# CarrierConnector.net
KiCad netlist of a schematic drawn in Altium Designer
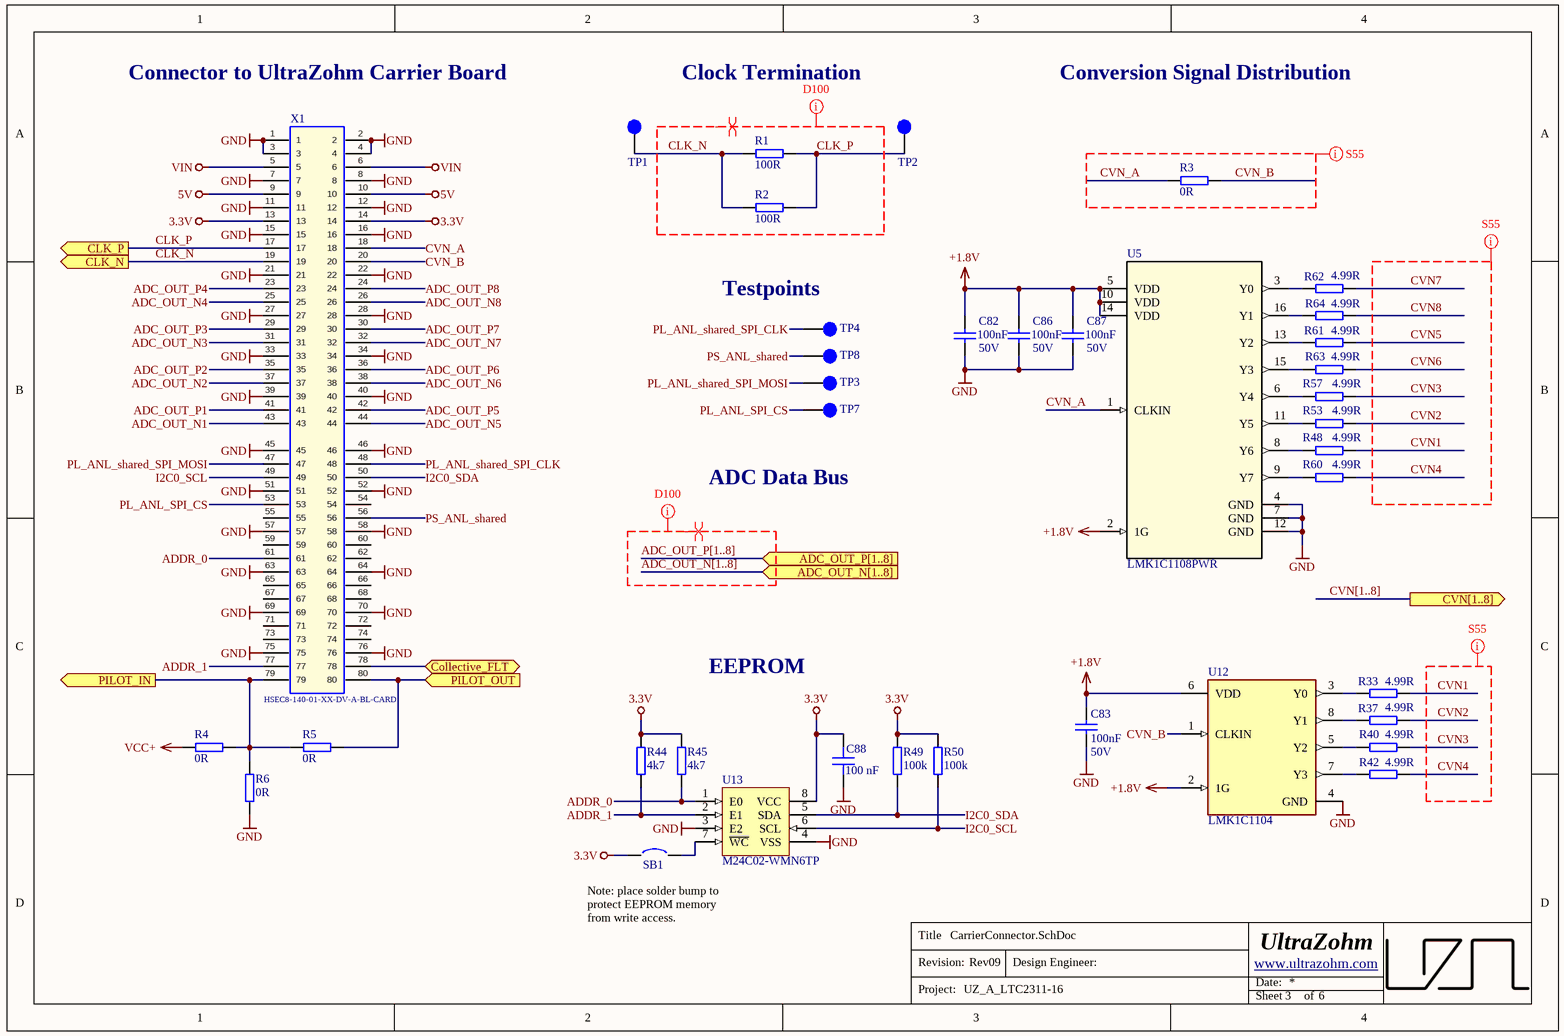
[diagram p0: CarrierConnector.SchDoc]

(export (version "E")
  (design (tool "Eeschema 10.0.6"))
  (components
    (comp (ref "C82")
      (value "100nF")
      (footprint "CAPC1608X07N")
      (fields
        (field (name "MF") "Yageo")
        (field (name "MPN") "CC0603KRX7R9BB104")
        (field (name "VOLTAGE") "50V")
      )
      (libsource (lib "UltraZohm_ADC") (part "Cap_0603"))
    )
    (comp (ref "C83")
      (value "100nF")
      (footprint "CAPC1608X07N")
      (fields
        (field (name "MF") "Yageo")
        (field (name "MPN") "CC0603KRX7R9BB104")
        (field (name "VOLTAGE") "50V")
      )
      (libsource (lib "UltraZohm_ADC") (part "Cap_0603"))
    )
    (comp (ref "C86")
      (value "100nF")
      (footprint "CAPC1608X07N")
      (fields
        (field (name "MF") "Yageo")
        (field (name "MPN") "CC0603KRX7R9BB104")
        (field (name "VOLTAGE") "50V")
      )
      (libsource (lib "UltraZohm_ADC") (part "Cap_0603"))
    )
    (comp (ref "C87")
      (value "100nF")
      (footprint "CAPC1608X07N")
      (fields
        (field (name "MF") "Yageo")
        (field (name "MPN") "CC0603KRX7R9BB104")
        (field (name "VOLTAGE") "50V")
      )
      (libsource (lib "UltraZohm_ADC") (part "Cap_0603"))
    )
    (comp (ref "C88")
      (value "100 nF")
      (footprint "C_0603")
      (description "Capacitor 0603, 6.3 VDC, 100 nF, X5R")
      (fields
        (field (name "MANUFACTURER PART NUMBER") "C0603C104K9PACTU")
        (field (name "MANUFACTURER") "KEMET")
        (field (name "CREATED FROM") "MGremer")
      )
      (libsource (lib "user") (part "Capacitor"))
    )
    (comp (ref "R1")
      (value "100R")
      (footprint "RESC1608X06N")
      (fields
        (field (name "MF") "Yageo")
        (field (name "MPN") "AC0603FR-13100RL")
        (field (name "TOLERANCE") "1%")
      )
      (libsource (lib "UltraZohm_ADC") (part "R_0603"))
    )
    (comp (ref "R2")
      (value "100R")
      (footprint "RESC1608X06N")
      (fields
        (field (name "MF") "Yageo")
        (field (name "MPN") "AC0603FR-13100RL")
        (field (name "TOLERANCE") "1%")
      )
      (libsource (lib "UltraZohm_ADC") (part "R_0603"))
    )
    (comp (ref "R3")
      (value "0R")
      (footprint "RESC1608X06N")
      (fields (field (name "MF") "Vishay / Dale") (field (name "MPN") "CRCW06030000Z0EBC"))
      (libsource (lib "UltraZohm_ADC") (part "R_0603"))
    )
    (comp (ref "R4")
      (value "0R")
      (footprint "RESC1608X06N")
      (fields (field (name "MF") "Vishay / Dale") (field (name "MPN") "CRCW06030000Z0EBC"))
      (libsource (lib "UltraZohm_ADC") (part "R_0603"))
    )
    (comp (ref "R5")
      (value "0R")
      (footprint "RESC1608X06N")
      (fields (field (name "MF") "Vishay / Dale") (field (name "MPN") "CRCW06030000Z0EBC"))
      (libsource (lib "UltraZohm_ADC") (part "R_0603"))
    )
    (comp (ref "R6")
      (value "0R")
      (footprint "RESC1608X06N")
      (fields (field (name "MF") "Vishay / Dale") (field (name "MPN") "CRCW06030000Z0EBC"))
      (libsource (lib "UltraZohm_ADC") (part "R_0603"))
    )
    (comp (ref "R33")
      (value "4.99R")
      (footprint "RESC1608X06N")
      (fields
        (field (name "MF") "Vishay / Dale")
        (field (name "MPN") "CRCW06034R99FKEA")
        (field (name "TOLERANCE") "1%")
      )
      (libsource (lib "UltraZohm_ADC") (part "R_0603"))
    )
    (comp (ref "R37")
      (value "4.99R")
      (footprint "RESC1608X06N")
      (fields
        (field (name "MF") "Vishay / Dale")
        (field (name "MPN") "CRCW06034R99FKEA")
        (field (name "TOLERANCE") "1%")
      )
      (libsource (lib "UltraZohm_ADC") (part "R_0603"))
    )
    (comp (ref "R40")
      (value "4.99R")
      (footprint "RESC1608X06N")
      (fields
        (field (name "MF") "Vishay / Dale")
        (field (name "MPN") "CRCW06034R99FKEA")
        (field (name "TOLERANCE") "1%")
      )
      (libsource (lib "UltraZohm_ADC") (part "R_0603"))
    )
    (comp (ref "R42")
      (value "4.99R")
      (footprint "RESC1608X06N")
      (fields
        (field (name "MF") "Vishay / Dale")
        (field (name "MPN") "CRCW06034R99FKEA")
        (field (name "TOLERANCE") "1%")
      )
      (libsource (lib "UltraZohm_ADC") (part "R_0603"))
    )
    (comp (ref "R44")
      (value "4k7")
      (footprint "RES 0603_1608")
      (description "SMD resistor E24 series")
      (fields
        (field (name "MANUFACTURER PART NUMBER") "0603WAF4701T5E")
        (field (name "MANUFACTURER") "UNI-ROYAL")
        (field (name "CREATED FROM") "AGeiger")
      )
      (libsource (lib "user") (part "Resistor"))
    )
    (comp (ref "R45")
      (value "4k7")
      (footprint "RES 0603_1608")
      (description "SMD resistor E24 series")
      (fields
        (field (name "MANUFACTURER PART NUMBER") "0603WAF4701T5E")
        (field (name "MANUFACTURER") "UNI-ROYAL")
        (field (name "CREATED FROM") "AGeiger")
      )
      (libsource (lib "user") (part "Resistor"))
    )
    (comp (ref "R48")
      (value "4.99R")
      (footprint "RESC1608X06N")
      (fields
        (field (name "MF") "Vishay / Dale")
        (field (name "MPN") "CRCW06034R99FKEA")
        (field (name "TOLERANCE") "1%")
      )
      (libsource (lib "UltraZohm_ADC") (part "R_0603"))
    )
    (comp (ref "R49")
      (value "100k")
      (footprint "RES 0603_1608")
      (description "SMD resistor E24 series")
      (fields
        (field (name "MANUFACTURER PART NUMBER") "RK73B1JTTD104J")
        (field (name "MANUFACTURER") "KOA Speer")
        (field (name "CREATED FROM") "MGremer")
      )
      (libsource (lib "user") (part "Resistor"))
    )
    (comp (ref "R50")
      (value "100k")
      (footprint "RES 0603_1608")
      (description "SMD resistor E24 series")
      (fields
        (field (name "MANUFACTURER PART NUMBER") "RK73B1JTTD104J")
        (field (name "MANUFACTURER") "KOA Speer")
        (field (name "CREATED FROM") "MGremer")
      )
      (libsource (lib "user") (part "Resistor"))
    )
    (comp (ref "R53")
      (value "4.99R")
      (footprint "RESC1608X06N")
      (fields
        (field (name "MF") "Vishay / Dale")
        (field (name "MPN") "CRCW06034R99FKEA")
        (field (name "TOLERANCE") "1%")
      )
      (libsource (lib "UltraZohm_ADC") (part "R_0603"))
    )
    (comp (ref "R57")
      (value "4.99R")
      (footprint "RESC1608X06N")
      (fields
        (field (name "MF") "Vishay / Dale")
        (field (name "MPN") "CRCW06034R99FKEA")
        (field (name "TOLERANCE") "1%")
      )
      (libsource (lib "UltraZohm_ADC") (part "R_0603"))
    )
    (comp (ref "R60")
      (value "4.99R")
      (footprint "RESC1608X06N")
      (fields
        (field (name "MF") "Vishay / Dale")
        (field (name "MPN") "CRCW06034R99FKEA")
        (field (name "TOLERANCE") "1%")
      )
      (libsource (lib "UltraZohm_ADC") (part "R_0603"))
    )
    (comp (ref "R61")
      (value "4.99R")
      (footprint "RESC1608X06N")
      (fields
        (field (name "MF") "Vishay / Dale")
        (field (name "MPN") "CRCW06034R99FKEA")
        (field (name "TOLERANCE") "1%")
      )
      (libsource (lib "UltraZohm_ADC") (part "R_0603"))
    )
    (comp (ref "R62")
      (value "4.99R")
      (footprint "RESC1608X06N")
      (fields
        (field (name "MF") "Vishay / Dale")
        (field (name "MPN") "CRCW06034R99FKEA")
        (field (name "TOLERANCE") "1%")
      )
      (libsource (lib "UltraZohm_ADC") (part "R_0603"))
    )
    (comp (ref "R63")
      (value "4.99R")
      (footprint "RESC1608X06N")
      (fields
        (field (name "MF") "Vishay / Dale")
        (field (name "MPN") "CRCW06034R99FKEA")
        (field (name "TOLERANCE") "1%")
      )
      (libsource (lib "UltraZohm_ADC") (part "R_0603"))
    )
    (comp (ref "R64")
      (value "4.99R")
      (footprint "RESC1608X06N")
      (fields
        (field (name "MF") "Vishay / Dale")
        (field (name "MPN") "CRCW06034R99FKEA")
        (field (name "TOLERANCE") "1%")
      )
      (libsource (lib "UltraZohm_ADC") (part "R_0603"))
    )
    (comp (ref "SB1")
      (value "Solder Bump 0603")
      (footprint "SB_0603")
      (fields (field (name "CREATED FROM") "AGeiger"))
      (libsource (lib "user") (part "Solder_Bump"))
    )
    (comp (ref "TP1")
      (value "ACLK_N")
      (footprint "TP_1mm")
      (description "Testpoint 1mm")
      (fields (field (name "CREATED") "2018_06_25_AGeiger"))
      (libsource (lib "UltraZOhm_CarrierBoard") (part "TP_1mm"))
    )
    (comp (ref "TP2")
      (value "ACLK_P")
      (footprint "TP_1mm")
      (description "Testpoint 1mm")
      (fields (field (name "CREATED") "2018_06_25_AGeiger"))
      (libsource (lib "UltraZOhm_CarrierBoard") (part "TP_1mm"))
    )
    (comp (ref "TP3")
      (value "PIN47")
      (footprint "TP_1mm")
      (description "Testpoint 1mm")
      (fields (field (name "CREATED") "2018_06_25_AGeiger"))
      (libsource (lib "UltraZOhm_CarrierBoard") (part "TP_1mm"))
    )
    (comp (ref "TP4")
      (value "PIN48")
      (footprint "TP_1mm")
      (description "Testpoint 1mm")
      (fields (field (name "CREATED") "2018_06_25_AGeiger"))
      (libsource (lib "UltraZOhm_CarrierBoard") (part "TP_1mm"))
    )
    (comp (ref "TP7")
      (value "PIN53")
      (footprint "TP_1mm")
      (description "Testpoint 1mm")
      (fields (field (name "CREATED") "2018_06_25_AGeiger"))
      (libsource (lib "UltraZOhm_CarrierBoard") (part "TP_1mm"))
    )
    (comp (ref "TP8")
      (value "PIN56")
      (footprint "TP_1mm")
      (description "Testpoint 1mm")
      (fields (field (name "CREATED") "2018_06_25_AGeiger"))
      (libsource (lib "UltraZOhm_CarrierBoard") (part "TP_1mm"))
    )
    (comp (ref "U5")
      (value "LMK1C1108PWR")
      (footprint "PW0016A_M")
      (description "8-channel output LVCMOS 1.8V buffer")
      (fields (field (name "MF") "Texas Instruments"))
      (libsource (lib "UltraZohm_ADC") (part "LMK1C1108PWR"))
    )
    (comp (ref "U12")
      (value "LMK1C1104")
      (footprint "FP-PW0008A-MFG")
      (description "4-channel output LVCMOS 1.8-V buffer")
      (fields
        (field (name "MANUFACTURER") "Texas Instruments")
        (field (name "MANUFACTURER PART NUMBER") "LMK1C1104PWR")
      )
      (libsource (lib "UltraZohm_ADC") (part "LMK1C1104"))
    )
    (comp (ref "U13")
      (value "M24C02-WMN6TP")
      (footprint "D0008A_N")
      (description "2Kbit I2C SOP-8 EEPROM ROHS")
      (fields
        (field (name "MANUFACTURER") "STMicroelectronics")
        (field (name "LCSC PART NUMBER") "C7562")
        (field (name "CREATED FROM") "AGeiger")
      )
      (libsource (lib "user") (part "M24256"))
    )
    (comp (ref "X1")
      (value "HSEC8-140-01-XX-DV-A-BL-CARD")
      (footprint "UZohmADC:HSEC8-140-01-XX-DV-A-BL-CARD")
      (description "Mating Card Layout for HSEC8-140-01-XX-DV-A-BL")
      (fields (field (name "MANUFACTURER") "SAMTEC") (field (name "CREATED") "2018_04_23_AGeiger"))
      (libsource (lib "UltraZohm_ADC") (part "HSEC8-140-01-XX-DV-A-BL-CARD"))
    )
  )
  (nets
    (net (code "1") (name "+1.8V") (class "Default")
      (node (ref "C82") (pin "1") (pinfunction "1_1") (pintype "passive"))
      (node (ref "C83") (pin "1") (pinfunction "1_1") (pintype "passive"))
      (node (ref "C86") (pin "1") (pinfunction "1_1") (pintype "passive"))
      (node (ref "C87") (pin "1") (pinfunction "1_1") (pintype "passive"))
      (node (ref "U12") (pin "2") (pinfunction "1G_2") (pintype "input"))
      (node (ref "U12") (pin "6") (pinfunction "VDD_6") (pintype "power_in"))
      (node (ref "U5") (pin "10") (pinfunction "VDD_10") (pintype "power_in"))
      (node (ref "U5") (pin "14") (pinfunction "VDD_14") (pintype "power_in"))
      (node (ref "U5") (pin "2") (pinfunction "1G_2") (pintype "input"))
      (node (ref "U5") (pin "5") (pinfunction "VDD_5") (pintype "power_in"))
    )
    (net (code "2") (name "/ADC_OUT_N1") (class "Default")
      (node (ref "X1") (pin "43") (pinfunction "43_43") (pintype "passive"))
    )
    (net (code "3") (name "/ADC_OUT_N2") (class "Default")
      (node (ref "X1") (pin "37") (pinfunction "37_37") (pintype "passive"))
    )
    (net (code "4") (name "/ADC_OUT_N3") (class "Default")
      (node (ref "X1") (pin "31") (pinfunction "31_31") (pintype "passive"))
    )
    (net (code "5") (name "/ADC_OUT_N4") (class "Default")
      (node (ref "X1") (pin "25") (pinfunction "25_25") (pintype "passive"))
    )
    (net (code "6") (name "/ADC_OUT_N5") (class "Default")
      (node (ref "X1") (pin "44") (pinfunction "44_44") (pintype "passive"))
    )
    (net (code "7") (name "/ADC_OUT_N6") (class "Default")
      (node (ref "X1") (pin "38") (pinfunction "38_38") (pintype "passive"))
    )
    (net (code "8") (name "/ADC_OUT_N7") (class "Default")
      (node (ref "X1") (pin "32") (pinfunction "32_32") (pintype "passive"))
    )
    (net (code "9") (name "/ADC_OUT_N8") (class "Default")
      (node (ref "X1") (pin "26") (pinfunction "26_26") (pintype "passive"))
    )
    (net (code "11") (name "/ADC_OUT_P1") (class "Default")
      (node (ref "X1") (pin "41") (pinfunction "41_41") (pintype "passive"))
    )
    (net (code "12") (name "/ADC_OUT_P2") (class "Default")
      (node (ref "X1") (pin "35") (pinfunction "35_35") (pintype "passive"))
    )
    (net (code "13") (name "/ADC_OUT_P3") (class "Default")
      (node (ref "X1") (pin "29") (pinfunction "29_29") (pintype "passive"))
    )
    (net (code "14") (name "/ADC_OUT_P4") (class "Default")
      (node (ref "X1") (pin "23") (pinfunction "23_23") (pintype "passive"))
    )
    (net (code "15") (name "/ADC_OUT_P5") (class "Default")
      (node (ref "X1") (pin "42") (pinfunction "42_42") (pintype "passive"))
    )
    (net (code "16") (name "/ADC_OUT_P6") (class "Default")
      (node (ref "X1") (pin "36") (pinfunction "36_36") (pintype "passive"))
    )
    (net (code "17") (name "/ADC_OUT_P7") (class "Default")
      (node (ref "X1") (pin "30") (pinfunction "30_30") (pintype "passive"))
    )
    (net (code "18") (name "/ADC_OUT_P8") (class "Default")
      (node (ref "X1") (pin "24") (pinfunction "24_24") (pintype "passive"))
    )
    (net (code "20") (name "/ADDR_0") (class "Default")
      (node (ref "R45") (pin "1") (pinfunction "1_1") (pintype "passive"))
      (node (ref "U13") (pin "1") (pinfunction "E0_1") (pintype "input"))
      (node (ref "X1") (pin "61") (pinfunction "61_61") (pintype "passive"))
    )
    (net (code "21") (name "/ADDR_1") (class "Default")
      (node (ref "R44") (pin "1") (pinfunction "1_1") (pintype "passive"))
      (node (ref "U13") (pin "2") (pinfunction "E1_2") (pintype "input"))
      (node (ref "X1") (pin "77") (pinfunction "77_77") (pintype "passive"))
    )
    (net (code "22") (name "/CLK_N") (class "Default")
      (node (ref "R1") (pin "1") (pintype "passive"))
      (node (ref "R2") (pin "1") (pintype "passive"))
      (node (ref "TP1") (pin "1") (pintype "passive"))
      (node (ref "X1") (pin "19") (pinfunction "19_19") (pintype "passive"))
    )
    (net (code "23") (name "/CLK_P") (class "Default")
      (node (ref "R1") (pin "2") (pintype "passive"))
      (node (ref "R2") (pin "2") (pintype "passive"))
      (node (ref "TP2") (pin "1") (pintype "passive"))
      (node (ref "X1") (pin "17") (pinfunction "17_17") (pintype "passive"))
    )
    (net (code "24") (name "/CVN1") (class "Default")
      (node (ref "R33") (pin "2") (pintype "passive"))
      (node (ref "R48") (pin "2") (pintype "passive"))
    )
    (net (code "25") (name "/CVN2") (class "Default")
      (node (ref "R37") (pin "2") (pintype "passive"))
      (node (ref "R53") (pin "2") (pintype "passive"))
    )
    (net (code "26") (name "/CVN3") (class "Default")
      (node (ref "R40") (pin "2") (pintype "passive"))
      (node (ref "R57") (pin "2") (pintype "passive"))
    )
    (net (code "27") (name "/CVN4") (class "Default")
      (node (ref "R42") (pin "2") (pintype "passive"))
      (node (ref "R60") (pin "2") (pintype "passive"))
    )
    (net (code "28") (name "/CVN5") (class "Default") (node (ref "R61") (pin "2") (pintype "passive")))
    (net (code "29") (name "/CVN6") (class "Default") (node (ref "R63") (pin "2") (pintype "passive")))
    (net (code "30") (name "/CVN7") (class "Default") (node (ref "R62") (pin "2") (pintype "passive")))
    (net (code "31") (name "/CVN8") (class "Default") (node (ref "R64") (pin "2") (pintype "passive")))
    (net (code "33") (name "/CVN_A") (class "Default")
      (node (ref "R3") (pin "1") (pintype "passive"))
      (node (ref "U5") (pin "1") (pinfunction "CLKIN_1") (pintype "input"))
      (node (ref "X1") (pin "18") (pinfunction "18_18") (pintype "passive"))
    )
    (net (code "34") (name "/CVN_B") (class "Default")
      (node (ref "R3") (pin "2") (pintype "passive"))
      (node (ref "U12") (pin "1") (pinfunction "CLKIN_1") (pintype "input"))
      (node (ref "X1") (pin "20") (pinfunction "20_20") (pintype "passive"))
    )
    (net (code "35") (name "/Collective_FLT") (class "Default")
      (node (ref "X1") (pin "78") (pinfunction "78_78") (pintype "passive"))
    )
    (net (code "36") (name "/I2C0_SCL") (class "Default")
      (node (ref "R50") (pin "1") (pinfunction "1_1") (pintype "passive"))
      (node (ref "U13") (pin "6") (pinfunction "SCL_6") (pintype "input"))
      (node (ref "X1") (pin "49") (pinfunction "49_49") (pintype "passive"))
    )
    (net (code "37") (name "/I2C0_SDA") (class "Default")
      (node (ref "R49") (pin "1") (pinfunction "1_1") (pintype "passive"))
      (node (ref "U13") (pin "5") (pinfunction "SDA_5") (pintype "open_collector"))
      (node (ref "X1") (pin "50") (pinfunction "50_50") (pintype "passive"))
    )
    (net (code "38") (name "/PILOT_IN") (class "Default")
      (node (ref "R4") (pin "2") (pintype "passive"))
      (node (ref "R5") (pin "1") (pintype "passive"))
      (node (ref "R6") (pin "2") (pintype "passive"))
      (node (ref "X1") (pin "79") (pinfunction "79_79") (pintype "passive"))
    )
    (net (code "39") (name "/PILOT_OUT") (class "Default")
      (node (ref "R5") (pin "2") (pintype "passive"))
      (node (ref "X1") (pin "80") (pinfunction "80_80") (pintype "passive"))
    )
    (net (code "40") (name "/PL_ANL_SPI_CS") (class "Default")
      (node (ref "TP7") (pin "1") (pintype "passive"))
      (node (ref "X1") (pin "53") (pinfunction "53_53") (pintype "passive"))
    )
    (net (code "41") (name "/PL_ANL_shared_SPI_CLK") (class "Default")
      (node (ref "TP4") (pin "1") (pintype "passive"))
      (node (ref "X1") (pin "48") (pinfunction "48_48") (pintype "passive"))
    )
    (net (code "42") (name "/PL_ANL_shared_SPI_MOSI") (class "Default")
      (node (ref "TP3") (pin "1") (pintype "passive"))
      (node (ref "X1") (pin "47") (pinfunction "47_47") (pintype "passive"))
    )
    (net (code "43") (name "/PS_ANL_shared") (class "Default")
      (node (ref "TP8") (pin "1") (pintype "passive"))
      (node (ref "X1") (pin "56") (pinfunction "56_56") (pintype "passive"))
    )
    (net (code "44") (name "3.3V") (class "Default")
      (node (ref "C88") (pin "1") (pinfunction "1_1") (pintype "passive"))
      (node (ref "R44") (pin "2") (pinfunction "2_2") (pintype "passive"))
      (node (ref "R45") (pin "2") (pinfunction "2_2") (pintype "passive"))
      (node (ref "R49") (pin "2") (pinfunction "2_2") (pintype "passive"))
      (node (ref "R50") (pin "2") (pinfunction "2_2") (pintype "passive"))
      (node (ref "SB1") (pin "1") (pinfunction "1_1") (pintype "passive"))
      (node (ref "U13") (pin "8") (pinfunction "VCC_8") (pintype "power_in"))
      (node (ref "X1") (pin "13") (pinfunction "13_13") (pintype "passive"))
      (node (ref "X1") (pin "14") (pinfunction "14_14") (pintype "passive"))
    )
    (net (code "45") (name "5V") (class "Default")
      (node (ref "X1") (pin "10") (pinfunction "10_10") (pintype "passive"))
      (node (ref "X1") (pin "9") (pinfunction "9_9") (pintype "passive"))
    )
    (net (code "46") (name "GND") (class "Default")
      (node (ref "C82") (pin "2") (pinfunction "2_2") (pintype "passive"))
      (node (ref "C83") (pin "2") (pinfunction "2_2") (pintype "passive"))
      (node (ref "C86") (pin "2") (pinfunction "2_2") (pintype "passive"))
      (node (ref "C87") (pin "2") (pinfunction "2_2") (pintype "passive"))
      (node (ref "C88") (pin "2") (pinfunction "2_2") (pintype "passive"))
      (node (ref "R6") (pin "1") (pintype "passive"))
      (node (ref "U12") (pin "4") (pinfunction "GND_4") (pintype "power_in"))
      (node (ref "U13") (pin "3") (pinfunction "E2_3") (pintype "input"))
      (node (ref "U13") (pin "4") (pinfunction "VSS_4") (pintype "power_in"))
      (node (ref "U5") (pin "12") (pinfunction "GND_12") (pintype "power_in"))
      (node (ref "U5") (pin "4") (pinfunction "GND_4") (pintype "power_in"))
      (node (ref "U5") (pin "7") (pinfunction "GND_7") (pintype "power_in"))
      (node (ref "X1") (pin "1") (pinfunction "1_1") (pintype "passive"))
      (node (ref "X1") (pin "11") (pinfunction "11_11") (pintype "passive"))
      (node (ref "X1") (pin "12") (pinfunction "12_12") (pintype "passive"))
      (node (ref "X1") (pin "15") (pinfunction "15_15") (pintype "passive"))
      (node (ref "X1") (pin "16") (pinfunction "16_16") (pintype "passive"))
      (node (ref "X1") (pin "2") (pinfunction "2_2") (pintype "passive"))
      (node (ref "X1") (pin "21") (pinfunction "21_21") (pintype "passive"))
      (node (ref "X1") (pin "22") (pinfunction "22_22") (pintype "passive"))
      (node (ref "X1") (pin "27") (pinfunction "27_27") (pintype "passive"))
      (node (ref "X1") (pin "28") (pinfunction "28_28") (pintype "passive"))
      (node (ref "X1") (pin "3") (pinfunction "3_3") (pintype "passive"))
      (node (ref "X1") (pin "33") (pinfunction "33_33") (pintype "passive"))
      (node (ref "X1") (pin "34") (pinfunction "34_34") (pintype "passive"))
      (node (ref "X1") (pin "39") (pinfunction "39_39") (pintype "passive"))
      (node (ref "X1") (pin "4") (pinfunction "4_4") (pintype "passive"))
      (node (ref "X1") (pin "40") (pinfunction "40_40") (pintype "passive"))
      (node (ref "X1") (pin "45") (pinfunction "45_45") (pintype "passive"))
      (node (ref "X1") (pin "46") (pinfunction "46_46") (pintype "passive"))
      (node (ref "X1") (pin "51") (pinfunction "51_51") (pintype "passive"))
      (node (ref "X1") (pin "52") (pinfunction "52_52") (pintype "passive"))
      (node (ref "X1") (pin "57") (pinfunction "57_57") (pintype "passive"))
      (node (ref "X1") (pin "58") (pinfunction "58_58") (pintype "passive"))
      (node (ref "X1") (pin "63") (pinfunction "63_63") (pintype "passive"))
      (node (ref "X1") (pin "64") (pinfunction "64_64") (pintype "passive"))
      (node (ref "X1") (pin "69") (pinfunction "69_69") (pintype "passive"))
      (node (ref "X1") (pin "7") (pinfunction "7_7") (pintype "passive"))
      (node (ref "X1") (pin "70") (pinfunction "70_70") (pintype "passive"))
      (node (ref "X1") (pin "75") (pinfunction "75_75") (pintype "passive"))
      (node (ref "X1") (pin "76") (pinfunction "76_76") (pintype "passive"))
      (node (ref "X1") (pin "8") (pinfunction "8_8") (pintype "passive"))
    )
    (net (code "47") (name "Net-(U5-Y0)") (class "Default")
      (node (ref "R62") (pin "1") (pintype "passive"))
      (node (ref "U5") (pin "3") (pinfunction "Y0_3") (pintype "output"))
    )
    (net (code "48") (name "Net-(U5-Y1)") (class "Default")
      (node (ref "R64") (pin "1") (pintype "passive"))
      (node (ref "U5") (pin "16") (pinfunction "Y1_16") (pintype "output"))
    )
    (net (code "49") (name "Net-(U5-Y2)") (class "Default")
      (node (ref "R61") (pin "1") (pintype "passive"))
      (node (ref "U5") (pin "13") (pinfunction "Y2_13") (pintype "output"))
    )
    (net (code "50") (name "Net-(U5-Y3)") (class "Default")
      (node (ref "R63") (pin "1") (pintype "passive"))
      (node (ref "U5") (pin "15") (pinfunction "Y3_15") (pintype "output"))
    )
    (net (code "51") (name "Net-(U5-Y4)") (class "Default")
      (node (ref "R57") (pin "1") (pintype "passive"))
      (node (ref "U5") (pin "6") (pinfunction "Y4_6") (pintype "output"))
    )
    (net (code "52") (name "Net-(U5-Y5)") (class "Default")
      (node (ref "R53") (pin "1") (pintype "passive"))
      (node (ref "U5") (pin "11") (pinfunction "Y5_11") (pintype "output"))
    )
    (net (code "53") (name "Net-(U5-Y6)") (class "Default")
      (node (ref "R48") (pin "1") (pintype "passive"))
      (node (ref "U5") (pin "8") (pinfunction "Y6_8") (pintype "output"))
    )
    (net (code "54") (name "Net-(U5-Y7)") (class "Default")
      (node (ref "R60") (pin "1") (pintype "passive"))
      (node (ref "U5") (pin "9") (pinfunction "Y7_9") (pintype "output"))
    )
    (net (code "55") (name "Net-(U12-Y0)") (class "Default")
      (node (ref "R33") (pin "1") (pintype "passive"))
      (node (ref "U12") (pin "3") (pinfunction "Y0_3") (pintype "output"))
    )
    (net (code "56") (name "Net-(U12-Y1)") (class "Default")
      (node (ref "R37") (pin "1") (pintype "passive"))
      (node (ref "U12") (pin "8") (pinfunction "Y1_8") (pintype "output"))
    )
    (net (code "57") (name "Net-(U12-Y2)") (class "Default")
      (node (ref "R40") (pin "1") (pintype "passive"))
      (node (ref "U12") (pin "5") (pinfunction "Y2_5") (pintype "output"))
    )
    (net (code "58") (name "Net-(U12-Y3)") (class "Default")
      (node (ref "R42") (pin "1") (pintype "passive"))
      (node (ref "U12") (pin "7") (pinfunction "Y3_7") (pintype "output"))
    )
    (net (code "59") (name "Net-(U13-~{WC})") (class "Default")
      (node (ref "SB1") (pin "2") (pinfunction "2_2") (pintype "passive"))
      (node (ref "U13") (pin "7") (pinfunction "~{WC}_7") (pintype "input"))
    )
    (net (code "60") (name "VCC+") (class "Default") (node (ref "R4") (pin "1") (pintype "passive")))
    (net (code "61") (name "VIN") (class "Default")
      (node (ref "X1") (pin "5") (pinfunction "5_5") (pintype "passive"))
      (node (ref "X1") (pin "6") (pinfunction "6_6") (pintype "passive"))
    )
    (net (code "62") (name "unconnected-(X1-Pad54)") (class "Default")
      (node (ref "X1") (pin "54") (pinfunction "54_54") (pintype "passive"))
    )
    (net (code "63") (name "unconnected-(X1-Pad55)") (class "Default")
      (node (ref "X1") (pin "55") (pinfunction "55_55") (pintype "passive"))
    )
    (net (code "64") (name "unconnected-(X1-Pad59)") (class "Default")
      (node (ref "X1") (pin "59") (pinfunction "59_59") (pintype "passive"))
    )
    (net (code "65") (name "unconnected-(X1-Pad60)") (class "Default")
      (node (ref "X1") (pin "60") (pinfunction "60_60") (pintype "passive"))
    )
    (net (code "66") (name "unconnected-(X1-Pad62)") (class "Default")
      (node (ref "X1") (pin "62") (pinfunction "62_62") (pintype "passive"))
    )
    (net (code "67") (name "unconnected-(X1-Pad65)") (class "Default")
      (node (ref "X1") (pin "65") (pinfunction "65_65") (pintype "passive"))
    )
    (net (code "68") (name "unconnected-(X1-Pad66)") (class "Default")
      (node (ref "X1") (pin "66") (pinfunction "66_66") (pintype "passive"))
    )
    (net (code "69") (name "unconnected-(X1-Pad67)") (class "Default")
      (node (ref "X1") (pin "67") (pinfunction "67_67") (pintype "passive"))
    )
    (net (code "70") (name "unconnected-(X1-Pad68)") (class "Default")
      (node (ref "X1") (pin "68") (pinfunction "68_68") (pintype "passive"))
    )
    (net (code "71") (name "unconnected-(X1-Pad71)") (class "Default")
      (node (ref "X1") (pin "71") (pinfunction "71_71") (pintype "passive"))
    )
    (net (code "72") (name "unconnected-(X1-Pad72)") (class "Default")
      (node (ref "X1") (pin "72") (pinfunction "72_72") (pintype "passive"))
    )
    (net (code "73") (name "unconnected-(X1-Pad73)") (class "Default")
      (node (ref "X1") (pin "73") (pinfunction "73_73") (pintype "passive"))
    )
    (net (code "74") (name "unconnected-(X1-Pad74)") (class "Default")
      (node (ref "X1") (pin "74") (pinfunction "74_74") (pintype "passive"))
    )
  )
)
